# STM32_Plate.net
KiCad netlist of a schematic drawn in Altium Designer
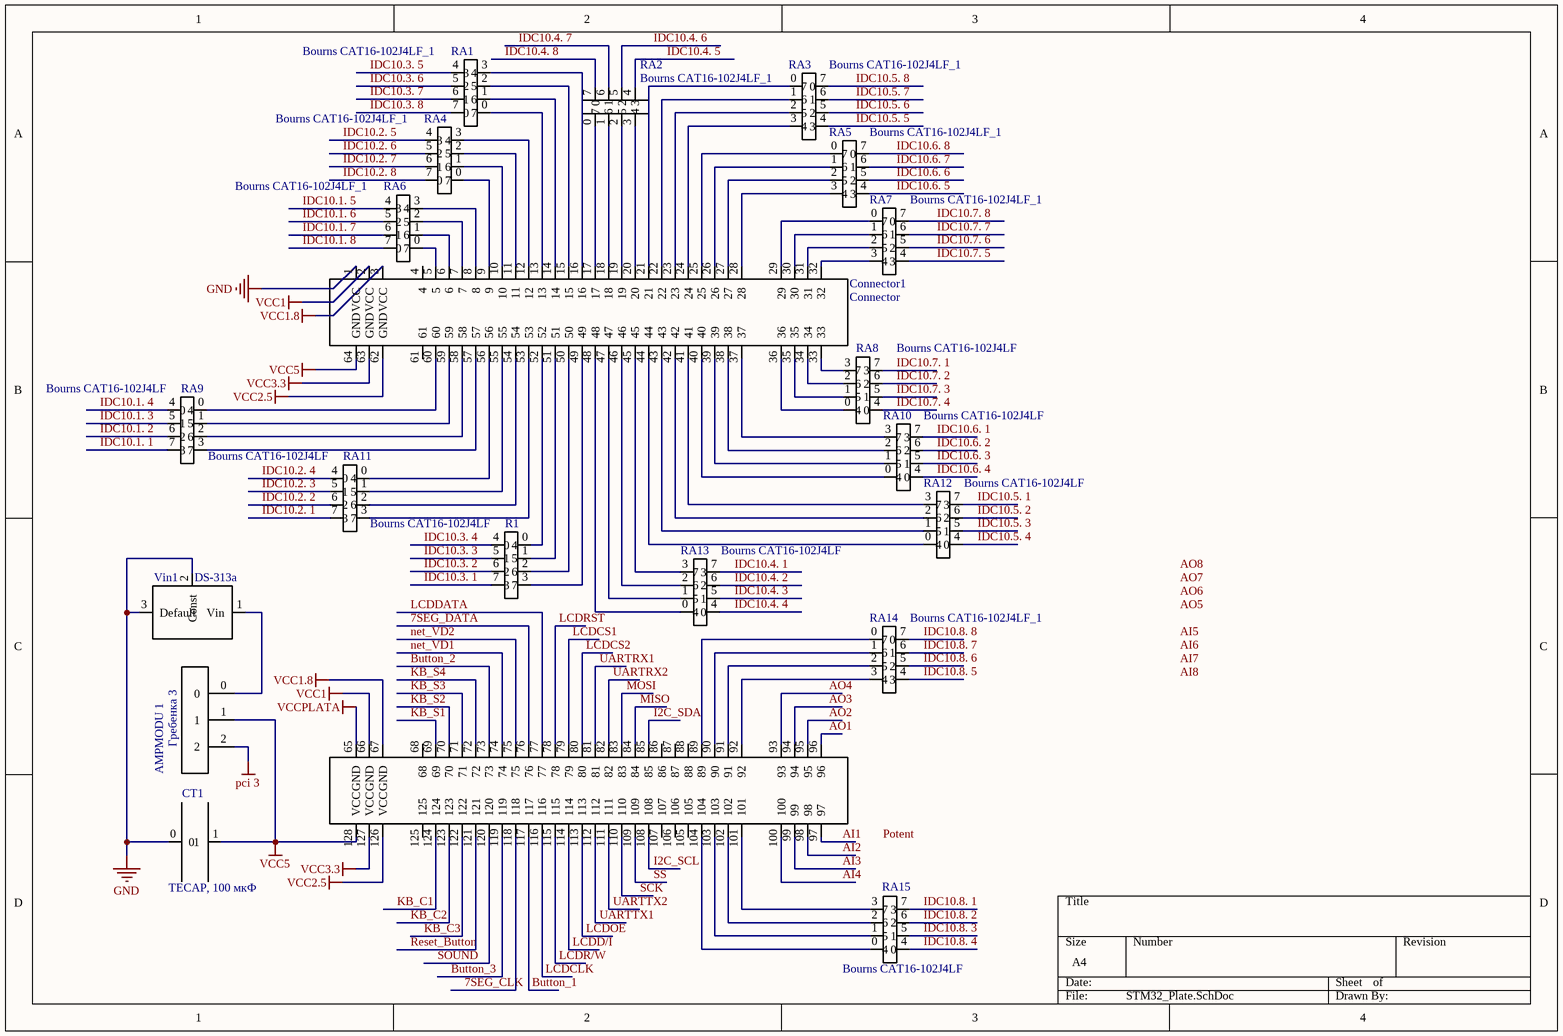
[diagram p0: STM32_Plate.SchDoc]

(export (version "E")
  (design (tool "Eeschema 10.0.6"))
  (components
    (comp (ref "AMPMODU 1")
      (value "Гребенка 3")
      (footprint "AMPMODU 826629-3")
      (libsource (lib "Library") (part "AMPMODU 826629-3"))
    )
    (comp (ref "Connector1")
      (value "Connector")
      (footprint "PcbLib1:Connect")
      (libsource (lib "Library") (part "Connector"))
    )
    (comp (ref "CT1")
      (value "TECAP, 100 мкФ")
      (footprint "PcbLib1:tantal cap")
      (libsource (lib "Library") (part "TECAP, 100 мкФ"))
    )
    (comp (ref "R1")
      (value "Bourns CAT16-102J4LF")
      (footprint "PcbLib1:CAT16-102J4LF")
      (libsource (lib "Library") (part "Bourns CAT16-102J4LF"))
    )
    (comp (ref "RA1")
      (value "Bourns CAT16-102J4LF_1")
      (footprint "PcbLib1:CAT16-102J4LF_2")
      (libsource (lib "Library") (part "Bourns CAT16-102J4LF_1"))
    )
    (comp (ref "RA2")
      (value "Bourns CAT16-102J4LF_1")
      (footprint "PcbLib1:CAT16-102J4LF_2")
      (libsource (lib "Library") (part "Bourns CAT16-102J4LF_1"))
    )
    (comp (ref "RA3")
      (value "Bourns CAT16-102J4LF_1")
      (footprint "PcbLib1:CAT16-102J4LF_2")
      (libsource (lib "Library") (part "Bourns CAT16-102J4LF_1"))
    )
    (comp (ref "RA4")
      (value "Bourns CAT16-102J4LF_1")
      (footprint "PcbLib1:CAT16-102J4LF_2")
      (libsource (lib "Library") (part "Bourns CAT16-102J4LF_1"))
    )
    (comp (ref "RA5")
      (value "Bourns CAT16-102J4LF_1")
      (footprint "PcbLib1:CAT16-102J4LF_2")
      (libsource (lib "Library") (part "Bourns CAT16-102J4LF_1"))
    )
    (comp (ref "RA6")
      (value "Bourns CAT16-102J4LF_1")
      (footprint "PcbLib1:CAT16-102J4LF_2")
      (libsource (lib "Library") (part "Bourns CAT16-102J4LF_1"))
    )
    (comp (ref "RA7")
      (value "Bourns CAT16-102J4LF_1")
      (footprint "PcbLib1:CAT16-102J4LF_2")
      (libsource (lib "Library") (part "Bourns CAT16-102J4LF_1"))
    )
    (comp (ref "RA8")
      (value "Bourns CAT16-102J4LF")
      (footprint "PcbLib1:CAT16-102J4LF")
      (libsource (lib "Library") (part "Bourns CAT16-102J4LF"))
    )
    (comp (ref "RA9")
      (value "Bourns CAT16-102J4LF")
      (footprint "PcbLib1:CAT16-102J4LF")
      (libsource (lib "Library") (part "Bourns CAT16-102J4LF"))
    )
    (comp (ref "RA10")
      (value "Bourns CAT16-102J4LF")
      (footprint "PcbLib1:CAT16-102J4LF")
      (libsource (lib "Library") (part "Bourns CAT16-102J4LF"))
    )
    (comp (ref "RA11")
      (value "Bourns CAT16-102J4LF")
      (footprint "PcbLib1:CAT16-102J4LF")
      (libsource (lib "Library") (part "Bourns CAT16-102J4LF"))
    )
    (comp (ref "RA12")
      (value "Bourns CAT16-102J4LF")
      (footprint "PcbLib1:CAT16-102J4LF")
      (libsource (lib "Library") (part "Bourns CAT16-102J4LF"))
    )
    (comp (ref "RA13")
      (value "Bourns CAT16-102J4LF")
      (footprint "PcbLib1:CAT16-102J4LF")
      (libsource (lib "Library") (part "Bourns CAT16-102J4LF"))
    )
    (comp (ref "RA14")
      (value "Bourns CAT16-102J4LF_1")
      (footprint "PcbLib1:CAT16-102J4LF_2")
      (libsource (lib "Library") (part "Bourns CAT16-102J4LF_1"))
    )
    (comp (ref "RA15")
      (value "Bourns CAT16-102J4LF")
      (footprint "PcbLib1:CAT16-102J4LF")
      (libsource (lib "Library") (part "Bourns CAT16-102J4LF"))
    )
    (comp (ref "Vin1")
      (value "DS-313a")
      (footprint "PcbLib1:ds-313")
      (libsource (lib "Library") (part "DS-313a"))
    )
  )
  (nets
    (net (code "1") (name "/7SEG_CLK") (class "Default")
      (node (ref "Connector1") (pin "118") (pinfunction "118_118") (pintype "passive"))
    )
    (net (code "2") (name "/7SEG_DATA") (class "Default")
      (node (ref "Connector1") (pin "76") (pinfunction "76_76") (pintype "passive"))
    )
    (net (code "3") (name "/AI1") (class "Default")
      (node (ref "Connector1") (pin "97") (pinfunction "97_97") (pintype "passive"))
    )
    (net (code "4") (name "/AI2") (class "Default")
      (node (ref "Connector1") (pin "98") (pinfunction "98_98") (pintype "passive"))
    )
    (net (code "5") (name "/AI3") (class "Default")
      (node (ref "Connector1") (pin "99") (pinfunction "99_99") (pintype "passive"))
    )
    (net (code "6") (name "/AI4") (class "Default")
      (node (ref "Connector1") (pin "100") (pinfunction "100_100") (pintype "passive"))
    )
    (net (code "11") (name "/AO1") (class "Default")
      (node (ref "Connector1") (pin "96") (pinfunction "96_96") (pintype "passive"))
    )
    (net (code "12") (name "/AO2") (class "Default")
      (node (ref "Connector1") (pin "95") (pinfunction "95_95") (pintype "passive"))
    )
    (net (code "13") (name "/AO3") (class "Default")
      (node (ref "Connector1") (pin "94") (pinfunction "94_94") (pintype "passive"))
    )
    (net (code "14") (name "/AO4") (class "Default")
      (node (ref "Connector1") (pin "93") (pinfunction "93_93") (pintype "passive"))
    )
    (net (code "19") (name "/Button_1") (class "Default")
      (node (ref "Connector1") (pin "117") (pinfunction "117_117") (pintype "passive"))
    )
    (net (code "20") (name "/Button_2") (class "Default")
      (node (ref "Connector1") (pin "73") (pinfunction "73_73") (pintype "passive"))
    )
    (net (code "21") (name "/Button_3") (class "Default")
      (node (ref "Connector1") (pin "119") (pinfunction "119_119") (pintype "passive"))
    )
    (net (code "22") (name "/I2C_SCL") (class "Default")
      (node (ref "Connector1") (pin "108") (pinfunction "108_108") (pintype "passive"))
    )
    (net (code "23") (name "/I2C_SDA") (class "Default")
      (node (ref "Connector1") (pin "85") (pinfunction "85_85") (pintype "passive"))
    )
    (net (code "24") (name "/IDC10.1. 1") (class "Default")
      (node (ref "RA9") (pin "7") (pinfunction "7_7") (pintype "passive"))
    )
    (net (code "25") (name "/IDC10.1. 2") (class "Default")
      (node (ref "RA9") (pin "6") (pinfunction "6_6") (pintype "passive"))
    )
    (net (code "26") (name "/IDC10.1. 3") (class "Default")
      (node (ref "RA9") (pin "5") (pinfunction "5_5") (pintype "passive"))
    )
    (net (code "27") (name "/IDC10.1. 4") (class "Default")
      (node (ref "RA9") (pin "4") (pinfunction "4_4") (pintype "passive"))
    )
    (net (code "28") (name "/IDC10.1. 5") (class "Default")
      (node (ref "RA6") (pin "4") (pinfunction "4_4") (pintype "passive"))
    )
    (net (code "29") (name "/IDC10.1. 6") (class "Default")
      (node (ref "RA6") (pin "5") (pinfunction "5_5") (pintype "passive"))
    )
    (net (code "30") (name "/IDC10.1. 7") (class "Default")
      (node (ref "RA6") (pin "6") (pinfunction "6_6") (pintype "passive"))
    )
    (net (code "31") (name "/IDC10.1. 8") (class "Default")
      (node (ref "RA6") (pin "7") (pinfunction "7_7") (pintype "passive"))
    )
    (net (code "32") (name "/IDC10.2. 1") (class "Default")
      (node (ref "RA11") (pin "7") (pinfunction "7_7") (pintype "passive"))
    )
    (net (code "33") (name "/IDC10.2. 2") (class "Default")
      (node (ref "RA11") (pin "6") (pinfunction "6_6") (pintype "passive"))
    )
    (net (code "34") (name "/IDC10.2. 3") (class "Default")
      (node (ref "RA11") (pin "5") (pinfunction "5_5") (pintype "passive"))
    )
    (net (code "35") (name "/IDC10.2. 4") (class "Default")
      (node (ref "RA11") (pin "4") (pinfunction "4_4") (pintype "passive"))
    )
    (net (code "36") (name "/IDC10.2. 5") (class "Default")
      (node (ref "RA4") (pin "4") (pinfunction "4_4") (pintype "passive"))
    )
    (net (code "37") (name "/IDC10.2. 6") (class "Default")
      (node (ref "RA4") (pin "5") (pinfunction "5_5") (pintype "passive"))
    )
    (net (code "38") (name "/IDC10.2. 7") (class "Default")
      (node (ref "RA4") (pin "6") (pinfunction "6_6") (pintype "passive"))
    )
    (net (code "39") (name "/IDC10.2. 8") (class "Default")
      (node (ref "RA4") (pin "7") (pinfunction "7_7") (pintype "passive"))
    )
    (net (code "40") (name "/IDC10.3. 1") (class "Default")
      (node (ref "R1") (pin "7") (pinfunction "7_7") (pintype "passive"))
    )
    (net (code "41") (name "/IDC10.3. 2") (class "Default")
      (node (ref "R1") (pin "6") (pinfunction "6_6") (pintype "passive"))
    )
    (net (code "42") (name "/IDC10.3. 3") (class "Default")
      (node (ref "R1") (pin "5") (pinfunction "5_5") (pintype "passive"))
    )
    (net (code "43") (name "/IDC10.3. 4") (class "Default")
      (node (ref "R1") (pin "4") (pinfunction "4_4") (pintype "passive"))
    )
    (net (code "44") (name "/IDC10.3. 5") (class "Default")
      (node (ref "RA1") (pin "4") (pinfunction "4_4") (pintype "passive"))
    )
    (net (code "45") (name "/IDC10.3. 6") (class "Default")
      (node (ref "RA1") (pin "5") (pinfunction "5_5") (pintype "passive"))
    )
    (net (code "46") (name "/IDC10.3. 7") (class "Default")
      (node (ref "RA1") (pin "6") (pinfunction "6_6") (pintype "passive"))
    )
    (net (code "47") (name "/IDC10.3. 8") (class "Default")
      (node (ref "RA1") (pin "7") (pinfunction "7_7") (pintype "passive"))
    )
    (net (code "48") (name "/IDC10.4. 1") (class "Default")
      (node (ref "RA13") (pin "7") (pinfunction "7_7") (pintype "passive"))
    )
    (net (code "49") (name "/IDC10.4. 2") (class "Default")
      (node (ref "RA13") (pin "6") (pinfunction "6_6") (pintype "passive"))
    )
    (net (code "50") (name "/IDC10.4. 3") (class "Default")
      (node (ref "RA13") (pin "5") (pinfunction "5_5") (pintype "passive"))
    )
    (net (code "51") (name "/IDC10.4. 4") (class "Default")
      (node (ref "RA13") (pin "4") (pinfunction "4_4") (pintype "passive"))
    )
    (net (code "52") (name "/IDC10.4. 5") (class "Default")
      (node (ref "RA2") (pin "4") (pinfunction "4_4") (pintype "passive"))
    )
    (net (code "53") (name "/IDC10.4. 6") (class "Default")
      (node (ref "RA2") (pin "5") (pinfunction "5_5") (pintype "passive"))
    )
    (net (code "54") (name "/IDC10.4. 7") (class "Default")
      (node (ref "RA2") (pin "6") (pinfunction "6_6") (pintype "passive"))
    )
    (net (code "55") (name "/IDC10.4. 8") (class "Default")
      (node (ref "RA2") (pin "7") (pinfunction "7_7") (pintype "passive"))
    )
    (net (code "56") (name "/IDC10.5. 1") (class "Default")
      (node (ref "RA12") (pin "7") (pinfunction "7_7") (pintype "passive"))
    )
    (net (code "57") (name "/IDC10.5. 2") (class "Default")
      (node (ref "RA12") (pin "6") (pinfunction "6_6") (pintype "passive"))
    )
    (net (code "58") (name "/IDC10.5. 3") (class "Default")
      (node (ref "RA12") (pin "5") (pinfunction "5_5") (pintype "passive"))
    )
    (net (code "59") (name "/IDC10.5. 4") (class "Default")
      (node (ref "RA12") (pin "4") (pinfunction "4_4") (pintype "passive"))
    )
    (net (code "60") (name "/IDC10.5. 5") (class "Default")
      (node (ref "RA3") (pin "4") (pinfunction "4_4") (pintype "passive"))
    )
    (net (code "61") (name "/IDC10.5. 6") (class "Default")
      (node (ref "RA3") (pin "5") (pinfunction "5_5") (pintype "passive"))
    )
    (net (code "62") (name "/IDC10.5. 7") (class "Default")
      (node (ref "RA3") (pin "6") (pinfunction "6_6") (pintype "passive"))
    )
    (net (code "63") (name "/IDC10.5. 8") (class "Default")
      (node (ref "RA3") (pin "7") (pinfunction "7_7") (pintype "passive"))
    )
    (net (code "64") (name "/IDC10.6. 1") (class "Default")
      (node (ref "RA10") (pin "7") (pinfunction "7_7") (pintype "passive"))
    )
    (net (code "65") (name "/IDC10.6. 2") (class "Default")
      (node (ref "RA10") (pin "6") (pinfunction "6_6") (pintype "passive"))
    )
    (net (code "66") (name "/IDC10.6. 3") (class "Default")
      (node (ref "RA10") (pin "5") (pinfunction "5_5") (pintype "passive"))
    )
    (net (code "67") (name "/IDC10.6. 4") (class "Default")
      (node (ref "RA10") (pin "4") (pinfunction "4_4") (pintype "passive"))
    )
    (net (code "68") (name "/IDC10.6. 5") (class "Default")
      (node (ref "RA5") (pin "4") (pinfunction "4_4") (pintype "passive"))
    )
    (net (code "69") (name "/IDC10.6. 6") (class "Default")
      (node (ref "RA5") (pin "5") (pinfunction "5_5") (pintype "passive"))
    )
    (net (code "70") (name "/IDC10.6. 7") (class "Default")
      (node (ref "RA5") (pin "6") (pinfunction "6_6") (pintype "passive"))
    )
    (net (code "71") (name "/IDC10.6. 8") (class "Default")
      (node (ref "RA5") (pin "7") (pinfunction "7_7") (pintype "passive"))
    )
    (net (code "72") (name "/IDC10.7. 1") (class "Default")
      (node (ref "RA8") (pin "7") (pinfunction "7_7") (pintype "passive"))
    )
    (net (code "73") (name "/IDC10.7. 2") (class "Default")
      (node (ref "RA8") (pin "6") (pinfunction "6_6") (pintype "passive"))
    )
    (net (code "74") (name "/IDC10.7. 3") (class "Default")
      (node (ref "RA8") (pin "5") (pinfunction "5_5") (pintype "passive"))
    )
    (net (code "75") (name "/IDC10.7. 4") (class "Default")
      (node (ref "RA8") (pin "4") (pinfunction "4_4") (pintype "passive"))
    )
    (net (code "76") (name "/IDC10.7. 5") (class "Default")
      (node (ref "RA7") (pin "4") (pinfunction "4_4") (pintype "passive"))
    )
    (net (code "77") (name "/IDC10.7. 6") (class "Default")
      (node (ref "RA7") (pin "5") (pinfunction "5_5") (pintype "passive"))
    )
    (net (code "78") (name "/IDC10.7. 7") (class "Default")
      (node (ref "RA7") (pin "6") (pinfunction "6_6") (pintype "passive"))
    )
    (net (code "79") (name "/IDC10.7. 8") (class "Default")
      (node (ref "RA7") (pin "7") (pinfunction "7_7") (pintype "passive"))
    )
    (net (code "80") (name "/IDC10.8. 1") (class "Default")
      (node (ref "RA15") (pin "7") (pinfunction "7_7") (pintype "passive"))
    )
    (net (code "81") (name "/IDC10.8. 2") (class "Default")
      (node (ref "RA15") (pin "6") (pinfunction "6_6") (pintype "passive"))
    )
    (net (code "82") (name "/IDC10.8. 3") (class "Default")
      (node (ref "RA15") (pin "5") (pinfunction "5_5") (pintype "passive"))
    )
    (net (code "83") (name "/IDC10.8. 4") (class "Default")
      (node (ref "RA15") (pin "4") (pinfunction "4_4") (pintype "passive"))
    )
    (net (code "84") (name "/IDC10.8. 5") (class "Default")
      (node (ref "RA14") (pin "4") (pinfunction "4_4") (pintype "passive"))
    )
    (net (code "85") (name "/IDC10.8. 6") (class "Default")
      (node (ref "RA14") (pin "5") (pinfunction "5_5") (pintype "passive"))
    )
    (net (code "86") (name "/IDC10.8. 7") (class "Default")
      (node (ref "RA14") (pin "6") (pinfunction "6_6") (pintype "passive"))
    )
    (net (code "87") (name "/IDC10.8. 8") (class "Default")
      (node (ref "RA14") (pin "7") (pinfunction "7_7") (pintype "passive"))
    )
    (net (code "88") (name "/KB_C1") (class "Default")
      (node (ref "Connector1") (pin "124") (pinfunction "124_124") (pintype "passive"))
    )
    (net (code "89") (name "/KB_C2") (class "Default")
      (node (ref "Connector1") (pin "123") (pinfunction "123_123") (pintype "passive"))
    )
    (net (code "90") (name "/KB_C3") (class "Default")
      (node (ref "Connector1") (pin "122") (pinfunction "122_122") (pintype "passive"))
    )
    (net (code "91") (name "/KB_S1") (class "Default")
      (node (ref "Connector1") (pin "69") (pinfunction "69_69") (pintype "passive"))
    )
    (net (code "92") (name "/KB_S2") (class "Default")
      (node (ref "Connector1") (pin "70") (pinfunction "70_70") (pintype "passive"))
    )
    (net (code "93") (name "/KB_S3") (class "Default")
      (node (ref "Connector1") (pin "71") (pinfunction "71_71") (pintype "passive"))
    )
    (net (code "94") (name "/KB_S4") (class "Default")
      (node (ref "Connector1") (pin "72") (pinfunction "72_72") (pintype "passive"))
    )
    (net (code "95") (name "/LCDCLK") (class "Default")
      (node (ref "Connector1") (pin "116") (pinfunction "116_116") (pintype "passive"))
    )
    (net (code "96") (name "/LCDCS1") (class "Default")
      (node (ref "Connector1") (pin "79") (pinfunction "79_79") (pintype "passive"))
    )
    (net (code "97") (name "/LCDCS2") (class "Default")
      (node (ref "Connector1") (pin "80") (pinfunction "80_80") (pintype "passive"))
    )
    (net (code "98") (name "/LCDDATA") (class "Default")
      (node (ref "Connector1") (pin "77") (pinfunction "77_77") (pintype "passive"))
    )
    (net (code "99") (name "/LCDD{slash}I") (class "Default")
      (node (ref "Connector1") (pin "114") (pinfunction "114_114") (pintype "passive"))
    )
    (net (code "100") (name "/LCDOE") (class "Default")
      (node (ref "Connector1") (pin "113") (pinfunction "113_113") (pintype "passive"))
    )
    (net (code "101") (name "/LCDRST") (class "Default")
      (node (ref "Connector1") (pin "78") (pinfunction "78_78") (pintype "passive"))
    )
    (net (code "102") (name "/LCDR{slash}W") (class "Default")
      (node (ref "Connector1") (pin "115") (pinfunction "115_115") (pintype "passive"))
    )
    (net (code "103") (name "/MISO") (class "Default")
      (node (ref "Connector1") (pin "84") (pinfunction "84_84") (pintype "passive"))
    )
    (net (code "104") (name "/MOSI") (class "Default")
      (node (ref "Connector1") (pin "83") (pinfunction "83_83") (pintype "passive"))
    )
    (net (code "106") (name "/Reset_Button") (class "Default")
      (node (ref "Connector1") (pin "121") (pinfunction "121_121") (pintype "passive"))
    )
    (net (code "107") (name "/SCK") (class "Default")
      (node (ref "Connector1") (pin "110") (pinfunction "110_110") (pintype "passive"))
    )
    (net (code "108") (name "/SOUND") (class "Default")
      (node (ref "Connector1") (pin "120") (pinfunction "120_120") (pintype "passive"))
    )
    (net (code "109") (name "/SS") (class "Default")
      (node (ref "Connector1") (pin "109") (pinfunction "109_109") (pintype "passive"))
    )
    (net (code "110") (name "/UARTRX1") (class "Default")
      (node (ref "Connector1") (pin "81") (pinfunction "81_81") (pintype "passive"))
    )
    (net (code "111") (name "/UARTRX2") (class "Default")
      (node (ref "Connector1") (pin "82") (pinfunction "82_82") (pintype "passive"))
    )
    (net (code "112") (name "/UARTTX1") (class "Default")
      (node (ref "Connector1") (pin "112") (pinfunction "112_112") (pintype "passive"))
    )
    (net (code "113") (name "/UARTTX2") (class "Default")
      (node (ref "Connector1") (pin "111") (pinfunction "111_111") (pintype "passive"))
    )
    (net (code "114") (name "/net_VD1") (class "Default")
      (node (ref "Connector1") (pin "74") (pinfunction "74_74") (pintype "passive"))
    )
    (net (code "115") (name "/net_VD2") (class "Default")
      (node (ref "Connector1") (pin "75") (pinfunction "75_75") (pintype "passive"))
    )
    (net (code "116") (name "GND") (class "Default")
      (node (ref "CT1") (pin "0") (pinfunction "0_0") (pintype "passive"))
      (node (ref "Connector1") (pin "1") (pinfunction "VCC_1") (pintype "passive"))
      (node (ref "Vin1") (pin "2") (pinfunction "Const_2") (pintype "passive"))
      (node (ref "Vin1") (pin "3") (pinfunction "Default_3") (pintype "passive"))
    )
    (net (code "117") (name "Net-(Connector1-Pad5)") (class "Default")
      (node (ref "Connector1") (pin "5") (pinfunction "5_5") (pintype "passive"))
      (node (ref "RA6") (pin "0") (pinfunction "0_0") (pintype "passive"))
    )
    (net (code "118") (name "Net-(Connector1-Pad6)") (class "Default")
      (node (ref "Connector1") (pin "6") (pinfunction "6_6") (pintype "passive"))
      (node (ref "RA6") (pin "1") (pinfunction "1_1") (pintype "passive"))
    )
    (net (code "119") (name "Net-(Connector1-Pad7)") (class "Default")
      (node (ref "Connector1") (pin "7") (pinfunction "7_7") (pintype "passive"))
      (node (ref "RA6") (pin "2") (pinfunction "2_2") (pintype "passive"))
    )
    (net (code "120") (name "Net-(Connector1-Pad8)") (class "Default")
      (node (ref "Connector1") (pin "8") (pinfunction "8_8") (pintype "passive"))
      (node (ref "RA6") (pin "3") (pinfunction "3_3") (pintype "passive"))
    )
    (net (code "121") (name "Net-(Connector1-Pad9)") (class "Default")
      (node (ref "Connector1") (pin "9") (pinfunction "9_9") (pintype "passive"))
      (node (ref "RA4") (pin "0") (pinfunction "0_0") (pintype "passive"))
    )
    (net (code "122") (name "Net-(Connector1-Pad10)") (class "Default")
      (node (ref "Connector1") (pin "10") (pinfunction "10_10") (pintype "passive"))
      (node (ref "RA4") (pin "1") (pinfunction "1_1") (pintype "passive"))
    )
    (net (code "123") (name "Net-(Connector1-Pad11)") (class "Default")
      (node (ref "Connector1") (pin "11") (pinfunction "11_11") (pintype "passive"))
      (node (ref "RA4") (pin "2") (pinfunction "2_2") (pintype "passive"))
    )
    (net (code "124") (name "Net-(Connector1-Pad12)") (class "Default")
      (node (ref "Connector1") (pin "12") (pinfunction "12_12") (pintype "passive"))
      (node (ref "RA4") (pin "3") (pinfunction "3_3") (pintype "passive"))
    )
    (net (code "125") (name "Net-(Connector1-Pad13)") (class "Default")
      (node (ref "Connector1") (pin "13") (pinfunction "13_13") (pintype "passive"))
      (node (ref "RA1") (pin "0") (pinfunction "0_0") (pintype "passive"))
    )
    (net (code "126") (name "Net-(Connector1-Pad14)") (class "Default")
      (node (ref "Connector1") (pin "14") (pinfunction "14_14") (pintype "passive"))
      (node (ref "RA1") (pin "1") (pinfunction "1_1") (pintype "passive"))
    )
    (net (code "127") (name "Net-(Connector1-Pad15)") (class "Default")
      (node (ref "Connector1") (pin "15") (pinfunction "15_15") (pintype "passive"))
      (node (ref "RA1") (pin "2") (pinfunction "2_2") (pintype "passive"))
    )
    (net (code "128") (name "Net-(Connector1-Pad16)") (class "Default")
      (node (ref "Connector1") (pin "16") (pinfunction "16_16") (pintype "passive"))
      (node (ref "RA1") (pin "3") (pinfunction "3_3") (pintype "passive"))
    )
    (net (code "129") (name "Net-(Connector1-Pad17)") (class "Default")
      (node (ref "Connector1") (pin "17") (pinfunction "17_17") (pintype "passive"))
      (node (ref "RA2") (pin "0") (pinfunction "0_0") (pintype "passive"))
    )
    (net (code "130") (name "Net-(Connector1-Pad18)") (class "Default")
      (node (ref "Connector1") (pin "18") (pinfunction "18_18") (pintype "passive"))
      (node (ref "RA2") (pin "1") (pinfunction "1_1") (pintype "passive"))
    )
    (net (code "131") (name "Net-(Connector1-Pad19)") (class "Default")
      (node (ref "Connector1") (pin "19") (pinfunction "19_19") (pintype "passive"))
      (node (ref "RA2") (pin "2") (pinfunction "2_2") (pintype "passive"))
    )
    (net (code "132") (name "Net-(Connector1-Pad20)") (class "Default")
      (node (ref "Connector1") (pin "20") (pinfunction "20_20") (pintype "passive"))
      (node (ref "RA2") (pin "3") (pinfunction "3_3") (pintype "passive"))
    )
    (net (code "133") (name "Net-(Connector1-Pad21)") (class "Default")
      (node (ref "Connector1") (pin "21") (pinfunction "21_21") (pintype "passive"))
      (node (ref "RA3") (pin "0") (pinfunction "0_0") (pintype "passive"))
    )
    (net (code "134") (name "Net-(Connector1-Pad22)") (class "Default")
      (node (ref "Connector1") (pin "22") (pinfunction "22_22") (pintype "passive"))
      (node (ref "RA3") (pin "1") (pinfunction "1_1") (pintype "passive"))
    )
    (net (code "135") (name "Net-(Connector1-Pad23)") (class "Default")
      (node (ref "Connector1") (pin "23") (pinfunction "23_23") (pintype "passive"))
      (node (ref "RA3") (pin "2") (pinfunction "2_2") (pintype "passive"))
    )
    (net (code "136") (name "Net-(Connector1-Pad24)") (class "Default")
      (node (ref "Connector1") (pin "24") (pinfunction "24_24") (pintype "passive"))
      (node (ref "RA3") (pin "3") (pinfunction "3_3") (pintype "passive"))
    )
    (net (code "137") (name "Net-(Connector1-Pad25)") (class "Default")
      (node (ref "Connector1") (pin "25") (pinfunction "25_25") (pintype "passive"))
      (node (ref "RA5") (pin "0") (pinfunction "0_0") (pintype "passive"))
    )
    (net (code "138") (name "Net-(Connector1-Pad26)") (class "Default")
      (node (ref "Connector1") (pin "26") (pinfunction "26_26") (pintype "passive"))
      (node (ref "RA5") (pin "1") (pinfunction "1_1") (pintype "passive"))
    )
    (net (code "139") (name "Net-(Connector1-Pad27)") (class "Default")
      (node (ref "Connector1") (pin "27") (pinfunction "27_27") (pintype "passive"))
      (node (ref "RA5") (pin "2") (pinfunction "2_2") (pintype "passive"))
    )
    (net (code "140") (name "Net-(Connector1-Pad28)") (class "Default")
      (node (ref "Connector1") (pin "28") (pinfunction "28_28") (pintype "passive"))
      (node (ref "RA5") (pin "3") (pinfunction "3_3") (pintype "passive"))
    )
    (net (code "141") (name "Net-(Connector1-Pad29)") (class "Default")
      (node (ref "Connector1") (pin "29") (pinfunction "29_29") (pintype "passive"))
      (node (ref "RA7") (pin "0") (pinfunction "0_0") (pintype "passive"))
    )
    (net (code "142") (name "Net-(Connector1-Pad30)") (class "Default")
      (node (ref "Connector1") (pin "30") (pinfunction "30_30") (pintype "passive"))
      (node (ref "RA7") (pin "1") (pinfunction "1_1") (pintype "passive"))
    )
    (net (code "143") (name "Net-(Connector1-Pad31)") (class "Default")
      (node (ref "Connector1") (pin "31") (pinfunction "31_31") (pintype "passive"))
      (node (ref "RA7") (pin "2") (pinfunction "2_2") (pintype "passive"))
    )
    (net (code "144") (name "Net-(Connector1-Pad32)") (class "Default")
      (node (ref "Connector1") (pin "32") (pinfunction "32_32") (pintype "passive"))
      (node (ref "RA7") (pin "3") (pinfunction "3_3") (pintype "passive"))
    )
    (net (code "145") (name "Net-(Connector1-Pad33)") (class "Default")
      (node (ref "Connector1") (pin "33") (pinfunction "33_33") (pintype "passive"))
      (node (ref "RA8") (pin "3") (pinfunction "3_3") (pintype "passive"))
    )
    (net (code "146") (name "Net-(Connector1-Pad34)") (class "Default")
      (node (ref "Connector1") (pin "34") (pinfunction "34_34") (pintype "passive"))
      (node (ref "RA8") (pin "2") (pinfunction "2_2") (pintype "passive"))
    )
    (net (code "147") (name "Net-(Connector1-Pad35)") (class "Default")
      (node (ref "Connector1") (pin "35") (pinfunction "35_35") (pintype "passive"))
      (node (ref "RA8") (pin "1") (pinfunction "1_1") (pintype "passive"))
    )
    (net (code "148") (name "Net-(Connector1-Pad36)") (class "Default")
      (node (ref "Connector1") (pin "36") (pinfunction "36_36") (pintype "passive"))
      (node (ref "RA8") (pin "0") (pinfunction "0_0") (pintype "passive"))
    )
    (net (code "149") (name "Net-(Connector1-Pad37)") (class "Default")
      (node (ref "Connector1") (pin "37") (pinfunction "37_37") (pintype "passive"))
      (node (ref "RA10") (pin "3") (pinfunction "3_3") (pintype "passive"))
    )
    (net (code "150") (name "Net-(Connector1-Pad38)") (class "Default")
      (node (ref "Connector1") (pin "38") (pinfunction "38_38") (pintype "passive"))
      (node (ref "RA10") (pin "2") (pinfunction "2_2") (pintype "passive"))
    )
    (net (code "151") (name "Net-(Connector1-Pad39)") (class "Default")
      (node (ref "Connector1") (pin "39") (pinfunction "39_39") (pintype "passive"))
      (node (ref "RA10") (pin "1") (pinfunction "1_1") (pintype "passive"))
    )
    (net (code "152") (name "Net-(Connector1-Pad40)") (class "Default")
      (node (ref "Connector1") (pin "40") (pinfunction "40_40") (pintype "passive"))
      (node (ref "RA10") (pin "0") (pinfunction "0_0") (pintype "passive"))
    )
    (net (code "153") (name "Net-(Connector1-Pad41)") (class "Default")
      (node (ref "Connector1") (pin "41") (pinfunction "41_41") (pintype "passive"))
      (node (ref "RA12") (pin "3") (pinfunction "3_3") (pintype "passive"))
    )
    (net (code "154") (name "Net-(Connector1-Pad42)") (class "Default")
      (node (ref "Connector1") (pin "42") (pinfunction "42_42") (pintype "passive"))
      (node (ref "RA12") (pin "2") (pinfunction "2_2") (pintype "passive"))
    )
    (net (code "155") (name "Net-(Connector1-Pad43)") (class "Default")
      (node (ref "Connector1") (pin "43") (pinfunction "43_43") (pintype "passive"))
      (node (ref "RA12") (pin "1") (pinfunction "1_1") (pintype "passive"))
    )
    (net (code "156") (name "Net-(Connector1-Pad44)") (class "Default")
      (node (ref "Connector1") (pin "44") (pinfunction "44_44") (pintype "passive"))
      (node (ref "RA12") (pin "0") (pinfunction "0_0") (pintype "passive"))
    )
    (net (code "157") (name "Net-(Connector1-Pad45)") (class "Default")
      (node (ref "Connector1") (pin "45") (pinfunction "45_45") (pintype "passive"))
      (node (ref "RA13") (pin "3") (pinfunction "3_3") (pintype "passive"))
    )
    (net (code "158") (name "Net-(Connector1-Pad46)") (class "Default")
      (node (ref "Connector1") (pin "46") (pinfunction "46_46") (pintype "passive"))
      (node (ref "RA13") (pin "2") (pinfunction "2_2") (pintype "passive"))
    )
    (net (code "159") (name "Net-(Connector1-Pad47)") (class "Default")
      (node (ref "Connector1") (pin "47") (pinfunction "47_47") (pintype "passive"))
      (node (ref "RA13") (pin "1") (pinfunction "1_1") (pintype "passive"))
    )
    (net (code "160") (name "Net-(Connector1-Pad48)") (class "Default")
      (node (ref "Connector1") (pin "48") (pinfunction "48_48") (pintype "passive"))
      (node (ref "RA13") (pin "0") (pinfunction "0_0") (pintype "passive"))
    )
    (net (code "161") (name "Net-(Connector1-Pad49)") (class "Default")
      (node (ref "Connector1") (pin "49") (pinfunction "49_49") (pintype "passive"))
      (node (ref "R1") (pin "3") (pinfunction "3_3") (pintype "passive"))
    )
    (net (code "162") (name "Net-(Connector1-Pad50)") (class "Default")
      (node (ref "Connector1") (pin "50") (pinfunction "50_50") (pintype "passive"))
      (node (ref "R1") (pin "2") (pinfunction "2_2") (pintype "passive"))
    )
    (net (code "163") (name "Net-(Connector1-Pad51)") (class "Default")
      (node (ref "Connector1") (pin "51") (pinfunction "51_51") (pintype "passive"))
      (node (ref "R1") (pin "1") (pinfunction "1_1") (pintype "passive"))
    )
    (net (code "164") (name "Net-(Connector1-Pad52)") (class "Default")
      (node (ref "Connector1") (pin "52") (pinfunction "52_52") (pintype "passive"))
      (node (ref "R1") (pin "0") (pinfunction "0_0") (pintype "passive"))
    )
    (net (code "165") (name "Net-(Connector1-Pad53)") (class "Default")
      (node (ref "Connector1") (pin "53") (pinfunction "53_53") (pintype "passive"))
      (node (ref "RA11") (pin "3") (pinfunction "3_3") (pintype "passive"))
    )
    (net (code "166") (name "Net-(Connector1-Pad54)") (class "Default")
      (node (ref "Connector1") (pin "54") (pinfunction "54_54") (pintype "passive"))
      (node (ref "RA11") (pin "2") (pinfunction "2_2") (pintype "passive"))
    )
    (net (code "167") (name "Net-(Connector1-Pad55)") (class "Default")
      (node (ref "Connector1") (pin "55") (pinfunction "55_55") (pintype "passive"))
      (node (ref "RA11") (pin "1") (pinfunction "1_1") (pintype "passive"))
    )
    (net (code "168") (name "Net-(Connector1-Pad56)") (class "Default")
      (node (ref "Connector1") (pin "56") (pinfunction "56_56") (pintype "passive"))
      (node (ref "RA11") (pin "0") (pinfunction "0_0") (pintype "passive"))
    )
    (net (code "169") (name "Net-(Connector1-Pad57)") (class "Default")
      (node (ref "Connector1") (pin "57") (pinfunction "57_57") (pintype "passive"))
      (node (ref "RA9") (pin "3") (pinfunction "3_3") (pintype "passive"))
    )
    (net (code "170") (name "Net-(Connector1-Pad58)") (class "Default")
      (node (ref "Connector1") (pin "58") (pinfunction "58_58") (pintype "passive"))
      (node (ref "RA9") (pin "2") (pinfunction "2_2") (pintype "passive"))
    )
    (net (code "171") (name "Net-(Connector1-Pad59)") (class "Default")
      (node (ref "Connector1") (pin "59") (pinfunction "59_59") (pintype "passive"))
      (node (ref "RA9") (pin "1") (pinfunction "1_1") (pintype "passive"))
    )
    (net (code "172") (name "Net-(Connector1-Pad60)") (class "Default")
      (node (ref "Connector1") (pin "60") (pinfunction "60_60") (pintype "passive"))
      (node (ref "RA9") (pin "0") (pinfunction "0_0") (pintype "passive"))
    )
    (net (code "173") (name "Net-(Connector1-Pad89)") (class "Default")
      (node (ref "Connector1") (pin "89") (pinfunction "89_89") (pintype "passive"))
      (node (ref "RA14") (pin "0") (pinfunction "0_0") (pintype "passive"))
    )
    (net (code "174") (name "Net-(Connector1-Pad90)") (class "Default")
      (node (ref "Connector1") (pin "90") (pinfunction "90_90") (pintype "passive"))
      (node (ref "RA14") (pin "1") (pinfunction "1_1") (pintype "passive"))
    )
    (net (code "175") (name "Net-(Connector1-Pad91)") (class "Default")
      (node (ref "Connector1") (pin "91") (pinfunction "91_91") (pintype "passive"))
      (node (ref "RA14") (pin "2") (pinfunction "2_2") (pintype "passive"))
    )
    (net (code "176") (name "Net-(Connector1-Pad92)") (class "Default")
      (node (ref "Connector1") (pin "92") (pinfunction "92_92") (pintype "passive"))
      (node (ref "RA14") (pin "3") (pinfunction "3_3") (pintype "passive"))
    )
    (net (code "177") (name "Net-(Connector1-Pad101)") (class "Default")
      (node (ref "Connector1") (pin "101") (pinfunction "101_101") (pintype "passive"))
      (node (ref "RA15") (pin "3") (pinfunction "3_3") (pintype "passive"))
    )
    (net (code "178") (name "Net-(Connector1-Pad102)") (class "Default")
      (node (ref "Connector1") (pin "102") (pinfunction "102_102") (pintype "passive"))
      (node (ref "RA15") (pin "2") (pinfunction "2_2") (pintype "passive"))
    )
    (net (code "179") (name "Net-(Connector1-Pad103)") (class "Default")
      (node (ref "Connector1") (pin "103") (pinfunction "103_103") (pintype "passive"))
      (node (ref "RA15") (pin "1") (pinfunction "1_1") (pintype "passive"))
    )
    (net (code "180") (name "Net-(Connector1-Pad104)") (class "Default")
      (node (ref "Connector1") (pin "104") (pinfunction "104_104") (pintype "passive"))
      (node (ref "RA15") (pin "0") (pinfunction "0_0") (pintype "passive"))
    )
    (net (code "181") (name "Net-(Vin1-Vin)") (class "Default")
      (node (ref "AMPMODU 1") (pin "0") (pinfunction "0_0") (pintype "passive"))
      (node (ref "Vin1") (pin "1") (pinfunction "Vin_1") (pintype "passive"))
    )
    (net (code "182") (name "VCC1") (class "Default")
      (node (ref "Connector1") (pin "2") (pinfunction "VCC_2") (pintype "passive"))
      (node (ref "Connector1") (pin "66") (pinfunction "GND_66") (pintype "passive"))
    )
    (net (code "183") (name "VCC1.8") (class "Default")
      (node (ref "Connector1") (pin "3") (pinfunction "VCC_3") (pintype "passive"))
      (node (ref "Connector1") (pin "67") (pinfunction "GND_67") (pintype "passive"))
    )
    (net (code "184") (name "VCC2.5") (class "Default")
      (node (ref "Connector1") (pin "126") (pinfunction "VCC_126") (pintype "passive"))
      (node (ref "Connector1") (pin "62") (pinfunction "GND_62") (pintype "passive"))
    )
    (net (code "185") (name "VCC3.3") (class "Default")
      (node (ref "Connector1") (pin "127") (pinfunction "VCC_127") (pintype "passive"))
      (node (ref "Connector1") (pin "63") (pinfunction "GND_63") (pintype "passive"))
    )
    (net (code "186") (name "VCC5") (class "Default")
      (node (ref "AMPMODU 1") (pin "1") (pinfunction "1_1") (pintype "passive"))
      (node (ref "CT1") (pin "1") (pinfunction "1_1") (pintype "passive"))
      (node (ref "Connector1") (pin "128") (pinfunction "VCC_128") (pintype "passive"))
      (node (ref "Connector1") (pin "64") (pinfunction "GND_64") (pintype "passive"))
    )
    (net (code "187") (name "VCCPLATA") (class "Default")
      (node (ref "Connector1") (pin "65") (pinfunction "GND_65") (pintype "passive"))
    )
    (net (code "188") (name "pci 3") (class "Default")
      (node (ref "AMPMODU 1") (pin "2") (pinfunction "2_2") (pintype "passive"))
    )
    (net (code "189") (name "unconnected-(Connector1-Pad4)") (class "Default")
      (node (ref "Connector1") (pin "4") (pinfunction "4_4") (pintype "passive"))
    )
    (net (code "190") (name "unconnected-(Connector1-Pad61)") (class "Default")
      (node (ref "Connector1") (pin "61") (pinfunction "61_61") (pintype "passive"))
    )
    (net (code "191") (name "unconnected-(Connector1-Pad68)") (class "Default")
      (node (ref "Connector1") (pin "68") (pinfunction "68_68") (pintype "passive"))
    )
    (net (code "192") (name "unconnected-(Connector1-Pad86)") (class "Default")
      (node (ref "Connector1") (pin "86") (pinfunction "86_86") (pintype "passive"))
    )
    (net (code "193") (name "unconnected-(Connector1-Pad87)") (class "Default")
      (node (ref "Connector1") (pin "87") (pinfunction "87_87") (pintype "passive"))
    )
    (net (code "194") (name "unconnected-(Connector1-Pad88)") (class "Default")
      (node (ref "Connector1") (pin "88") (pinfunction "88_88") (pintype "passive"))
    )
    (net (code "195") (name "unconnected-(Connector1-Pad105)") (class "Default")
      (node (ref "Connector1") (pin "105") (pinfunction "105_105") (pintype "passive"))
    )
    (net (code "196") (name "unconnected-(Connector1-Pad106)") (class "Default")
      (node (ref "Connector1") (pin "106") (pinfunction "106_106") (pintype "passive"))
    )
    (net (code "197") (name "unconnected-(Connector1-Pad107)") (class "Default")
      (node (ref "Connector1") (pin "107") (pinfunction "107_107") (pintype "passive"))
    )
    (net (code "198") (name "unconnected-(Connector1-Pad125)") (class "Default")
      (node (ref "Connector1") (pin "125") (pinfunction "125_125") (pintype "passive"))
    )
  )
)
